# TSAL_REV2.net
KiCad netlist of a schematic drawn in Altium Designer
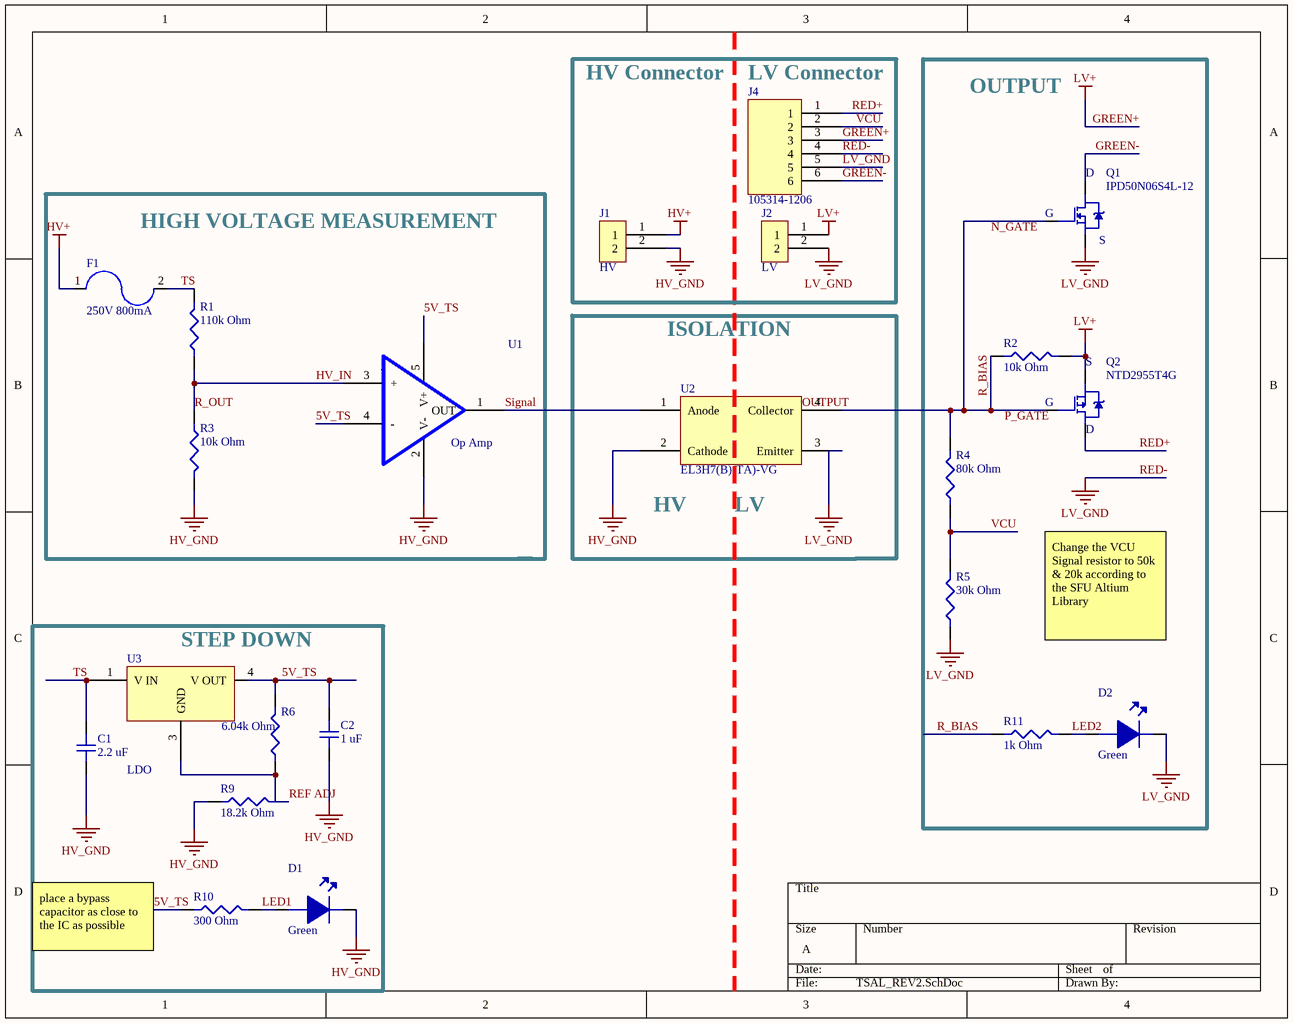
[diagram p0: TSAL_REV2.SchDoc]

(export (version "E")
  (design (tool "Eeschema 10.0.6"))
  (components
    (comp (ref "C1")
      (value "2.2 uF")
      (footprint "CAPC5850X25N")
      (description "CAP CER 2.2UF 250V X7T 2220")
      (fields
        (field (name "MANUFACTURER") "TDK")
        (field (name "MANUFACTURER PART NUMBER") "CGA9P3X7T2E225K250KE")
      )
      (libsource (lib "TSAL_REV1") (part "CGA9P3X7T2E225K250KE"))
    )
    (comp (ref "C2")
      (value "1 uF")
      (description "Cap Ceramic 1uF 10V X5R 10% SMD 0603 85C Paper T/R")
      (fields
        (field (name "MANUFACTURER") "Samsung")
        (field (name "MANUFACTURER PART NUMBER") "CL10A105KP8NNNC")
      )
      (libsource (lib "TSAL_REV1") (part "CL10A105KP8NNNC"))
    )
    (comp (ref "D1")
      (value "Green")
      (footprint "LED_0603")
      (description "LED Uni-Color Green 574nm 2-Pin Chip LED T/R")
      (fields
        (field (name "MANUFACTURER") "Vishay Lite-On")
        (field (name "MANUFACTURER PART NUMBER") "LTST-C191KGKT")
      )
      (libsource (lib "TSAL_REV1") (part "LTST-C191KGKT"))
    )
    (comp (ref "D2")
      (value "Green")
      (footprint "LED_0603")
      (description "LED Uni-Color Green 574nm 2-Pin Chip LED T/R")
      (fields
        (field (name "MANUFACTURER") "Vishay Lite-On")
        (field (name "MANUFACTURER PART NUMBER") "LTST-C191KGKT")
      )
      (libsource (lib "TSAL_REV1") (part "LTST-C191KGKT"))
    )
    (comp (ref "F1")
      (value "250V 800mA")
      (footprint "FUSE_SMD")
      (fields (field (name "MANUFACTURER") "Bel") (field (name "MANUFACTURER PART NUMBER") "0678D0800-02"))
      (libsource (lib "TSAL_REV1") (part "0678D0800-02"))
    )
    (comp (ref "J1")
      (value "HV")
      (footprint "2_PIN_CONNECTOR")
      (fields (field (name "MANUFACTURER") "Molex") (field (name "MANUFACTURER PART NUMBER") "0705530001"))
      (libsource (lib "TSAL_REV1") (part "0705530001"))
    )
    (comp (ref "J2")
      (value "LV")
      (footprint "2_PIN_CONNECTOR")
      (fields (field (name "MANUFACTURER") "Molex") (field (name "MANUFACTURER PART NUMBER") "0705530001"))
      (libsource (lib "TSAL_REV1") (part "0705530001"))
    )
    (comp (ref "J4")
      (value "105314-1206")
      (footprint "*MOLEX_1053141206")
      (description "CONN HEADER R/A 6POS 2.5MM")
      (fields (field (name "MANUFACTURER") "Molex"))
      (libsource (lib "TSAL_REV1") (part "105314-1206"))
    )
    (comp (ref "Q1")
      (value "IPD50N06S4L-12")
      (footprint "DPAK228P998X235-3N")
      (description "MOSFET N-CH 60V 50A TO252-3-11")
      (fields (field (name "MANUFACTURER") "Infineon"))
      (libsource (lib "TSAL_REV1") (part "IPD50N06S4L-12"))
    )
    (comp (ref "Q2")
      (value "NTD2955T4G")
      (footprint "DPAK228P991X238-3N")
      (description "Trans MOSFET P-CH 60V 12A 3-Pin(2+Tab) DPAK T/R")
      (fields (field (name "MANUFACTURER") "ON Semiconductor"))
      (libsource (lib "TSAL_REV1") (part "NTD2955T4G"))
    )
    (comp (ref "R1")
      (value "110k Ohm")
      (footprint "RESC3116X06N")
      (description "RES SMD 110K OHM 1% 1/4W 1206")
      (fields
        (field (name "MANUFACTURER") "Yageo")
        (field (name "MANUFACTURER PART NUMBER") "RC1206FR-07110KL")
      )
      (libsource (lib "TSAL_REV1") (part "RC1206FR-07110KL"))
    )
    (comp (ref "R2")
      (value "10k Ohm")
      (footprint "RESC2012X06N")
      (description "RES 10K OHM 1% 1/4W 0805")
      (fields
        (field (name "MANUFACTURER") "Stackpole Electronics")
        (field (name "MANUFACTURER PART NUMBER") "RNCP0805FTD10K0")
      )
      (libsource (lib "TSAL_REV1") (part "RNCP0805FTD10K0"))
    )
    (comp (ref "R3")
      (value "10k Ohm")
      (footprint "RESC2012X06N")
      (description "RES 10K OHM 1% 1/4W 0805")
      (fields
        (field (name "MANUFACTURER") "Stackpole Electronics")
        (field (name "MANUFACTURER PART NUMBER") "RNCP0805FTD10K0")
      )
      (libsource (lib "TSAL_REV1") (part "RNCP0805FTD10K0"))
    )
    (comp (ref "R4")
      (value "80k Ohm")
      (footprint "RESC1608X06N")
      (description "RES 80K OHM 0.1% 0.15W 0603")
      (fields
        (field (name "MANUFACTURER") "Vishay Dale")
        (field (name "MANUFACTURER PART NUMBER") "PTN0603E8002BST1")
      )
      (libsource (lib "TSAL_REV1") (part "PTN0603E8002BST1"))
    )
    (comp (ref "R5")
      (value "30k Ohm")
      (footprint "RESC2012X06N")
      (description "Thick Film Resistors CRG0805 1% 30K")
      (fields
        (field (name "MANUFACTURER") "TE Connectivity")
        (field (name "MANUFACTURER PART NUMBER") "CRG0805F30K")
      )
      (libsource (lib "TSAL_REV1") (part "CRG0805F30K"))
    )
    (comp (ref "R6")
      (value "6.04k Ohm")
      (footprint "RESC2012X06N")
      (description "RES SMD 6.04KOHM 0.5% 1/10W 0805")
      (fields
        (field (name "MANUFACTURER") "Susumu")
        (field (name "MANUFACTURER PART NUMBER") "RR1220P-6041-D-M")
      )
      (libsource (lib "TSAL_REV1") (part "RR1220P-6041-D-M"))
    )
    (comp (ref "R9")
      (value "18.2k Ohm")
      (footprint "RESC2012X06N")
      (description "Panasonic ERA Series Thin Film Surface Mount Resistor 0805 Case 18.2k 0.1% 0.125W 25ppm/C")
      (fields
        (field (name "MANUFACTURER") "Panasonic")
        (field (name "MANUFACTURER PART NUMBER") "ERA-6AEB1822V")
      )
      (libsource (lib "TSAL_REV1") (part "ERA-6AEB1822V"))
    )
    (comp (ref "R10")
      (value "300 Ohm")
      (footprint "RESC1608X06N")
      (description "RES SMD 300 OHM 0.5% 1/16W 0603")
      (fields
        (field (name "MANUFACTURER") "Susumu")
        (field (name "MANUFACTURER PART NUMBER") "RR0816P-301-D")
      )
      (libsource (lib "TSAL_REV1") (part "RR0816P-301-D"))
    )
    (comp (ref "R11")
      (value "1k Ohm")
      (footprint "RESC1608X06N")
      (description "RES SMD 1K OHM 5% 1/10W 0603")
      (fields
        (field (name "MANUFACTURER") "Yageo")
        (field (name "MANUFACTURER PART NUMBER") "RC0603JR-071KL")
      )
      (libsource (lib "TSAL_REV1") (part "RC0603JR-071KL"))
    )
    (comp (ref "U1")
      (value "Op Amp")
      (footprint "SOT95P280X145-5N")
      (description "MICROCHIP - MCP6001T-I/OT - OP AMP, 1MHZ, 0.6V/uS, SOT-23-5, FULL REEL")
      (fields
        (field (name "MANUFACTURER") "Microchip")
        (field (name "MANUFACTURER PART NUMBER") "MCP6001T-I/OT")
      )
      (libsource (lib "TSAL_REV1_1_SchematicLib ") (part "MCP6001T-I/OT"))
    )
    (comp (ref "U2")
      (value "EL3H7(B)(TA)-VG")
      (footprint "SOIC127P700X200-4N")
      (description "OPTOISOLATOR 3.75KV TRANS 4-SSOP")
      (fields (field (name "MANUFACTURER") "Everlight"))
      (libsource (lib "TSAL_REV1") (part "EL3H7(B)(TA)-VG"))
    )
    (comp (ref "U3")
      (value "LDO")
      (footprint "DPAK228P998X235-3N")
      (description "Standard Regulator Pos 1.2V to 440V 0.01A 3-Pin(2+Tab) TO-252")
      (fields (field (name "MANUFACTURER") "Microchip") (field (name "MANUFACTURER PART NUMBER") "LR8K4-G"))
      (libsource (lib "TSAL_REV1") (part "LR8K4-G"))
    )
  )
  (nets
    (net (code "1") (name "/5V_TS") (class "Default")
      (node (ref "C2") (pin "2") (pinfunction "2_2") (pintype "passive"))
      (node (ref "R10") (pin "1") (pinfunction "1_1") (pintype "passive"))
      (node (ref "R6") (pin "2") (pinfunction "2_2") (pintype "passive"))
      (node (ref "U1") (pin "4") (pinfunction "-_4") (pintype "passive"))
      (node (ref "U1") (pin "5") (pinfunction "V+_5") (pintype "passive"))
      (node (ref "U3") (pin "4") (pinfunction "V_OUT_4") (pintype "passive"))
    )
    (net (code "2") (name "/GREEN-") (class "Default")
      (node (ref "J4") (pin "6") (pinfunction "6_6") (pintype "passive"))
      (node (ref "Q1") (pin "4") (pinfunction "4_4") (pintype "passive"))
    )
    (net (code "3") (name "/HV_IN") (class "Default")
      (node (ref "R1") (pin "1") (pinfunction "1_1") (pintype "passive"))
      (node (ref "R3") (pin "1") (pinfunction "1_1") (pintype "passive"))
      (node (ref "U1") (pin "3") (pinfunction "+_3") (pintype "passive"))
    )
    (net (code "4") (name "/LED1") (class "Default")
      (node (ref "D1") (pin "1") (pinfunction "1_1") (pintype "passive"))
      (node (ref "R10") (pin "2") (pinfunction "2_2") (pintype "passive"))
    )
    (net (code "5") (name "/LED2") (class "Default")
      (node (ref "D2") (pin "1") (pinfunction "1_1") (pintype "passive"))
      (node (ref "R11") (pin "2") (pinfunction "2_2") (pintype "passive"))
    )
    (net (code "9") (name "/RED+") (class "Default")
      (node (ref "J4") (pin "1") (pinfunction "1_1") (pintype "passive"))
      (node (ref "Q2") (pin "3") (pinfunction "3_3") (pintype "passive"))
    )
    (net (code "10") (name "/REF ADJ") (class "Default")
      (node (ref "R6") (pin "1") (pinfunction "1_1") (pintype "passive"))
      (node (ref "R9") (pin "2") (pinfunction "2_2") (pintype "passive"))
      (node (ref "U3") (pin "3") (pinfunction "GND_3") (pintype "passive"))
    )
    (net (code "11") (name "/R_BIAS") (class "Default")
      (node (ref "Q1") (pin "1") (pinfunction "1_1") (pintype "passive"))
      (node (ref "Q2") (pin "1") (pinfunction "1_1") (pintype "passive"))
      (node (ref "R11") (pin "1") (pinfunction "1_1") (pintype "passive"))
      (node (ref "R2") (pin "1") (pinfunction "1_1") (pintype "passive"))
      (node (ref "R4") (pin "2") (pinfunction "2_2") (pintype "passive"))
      (node (ref "U2") (pin "4") (pinfunction "Collector_4") (pintype "passive"))
    )
    (net (code "12") (name "/Signal") (class "Default")
      (node (ref "U1") (pin "1") (pinfunction "OUT_1") (pintype "passive"))
      (node (ref "U2") (pin "1") (pinfunction "Anode_1") (pintype "passive"))
    )
    (net (code "13") (name "/TS") (class "Default")
      (node (ref "C1") (pin "2") (pinfunction "2_2") (pintype "passive"))
      (node (ref "F1") (pin "2") (pinfunction "2_2") (pintype "passive"))
      (node (ref "R1") (pin "2") (pinfunction "2_2") (pintype "passive"))
      (node (ref "U3") (pin "1") (pinfunction "V_IN_1") (pintype "passive"))
    )
    (net (code "14") (name "/VCU") (class "Default")
      (node (ref "J4") (pin "2") (pinfunction "2_2") (pintype "passive"))
      (node (ref "R4") (pin "1") (pinfunction "1_1") (pintype "passive"))
      (node (ref "R5") (pin "2") (pinfunction "2_2") (pintype "passive"))
    )
    (net (code "15") (name "HV+") (class "Default")
      (node (ref "F1") (pin "1") (pinfunction "1_1") (pintype "passive"))
      (node (ref "J1") (pin "1") (pinfunction "1_1") (pintype "passive"))
    )
    (net (code "16") (name "HV_GND") (class "Default")
      (node (ref "C1") (pin "1") (pinfunction "1_1") (pintype "passive"))
      (node (ref "C2") (pin "1") (pinfunction "1_1") (pintype "passive"))
      (node (ref "D1") (pin "2") (pinfunction "2_2") (pintype "passive"))
      (node (ref "J1") (pin "2") (pinfunction "2_2") (pintype "passive"))
      (node (ref "R3") (pin "2") (pinfunction "2_2") (pintype "passive"))
      (node (ref "R9") (pin "1") (pinfunction "1_1") (pintype "passive"))
      (node (ref "U1") (pin "2") (pinfunction "V-_2") (pintype "passive"))
      (node (ref "U2") (pin "2") (pinfunction "Cathode_2") (pintype "passive"))
    )
    (net (code "17") (name "LV+") (class "Default")
      (node (ref "J2") (pin "1") (pinfunction "1_1") (pintype "passive"))
      (node (ref "J4") (pin "3") (pinfunction "3_3") (pintype "passive"))
      (node (ref "Q2") (pin "4") (pinfunction "4_4") (pintype "passive"))
      (node (ref "R2") (pin "2") (pinfunction "2_2") (pintype "passive"))
    )
    (net (code "18") (name "LV_GND") (class "Default")
      (node (ref "D2") (pin "2") (pinfunction "2_2") (pintype "passive"))
      (node (ref "J2") (pin "2") (pinfunction "2_2") (pintype "passive"))
      (node (ref "J4") (pin "4") (pinfunction "4_4") (pintype "passive"))
      (node (ref "J4") (pin "5") (pinfunction "5_5") (pintype "passive"))
      (node (ref "Q1") (pin "3") (pinfunction "3_3") (pintype "passive"))
      (node (ref "R5") (pin "1") (pinfunction "1_1") (pintype "passive"))
      (node (ref "U2") (pin "3") (pinfunction "Emitter_3") (pintype "passive"))
    )
  )
)
